# Main.net
KiCad netlist of a schematic drawn in Altium Designer
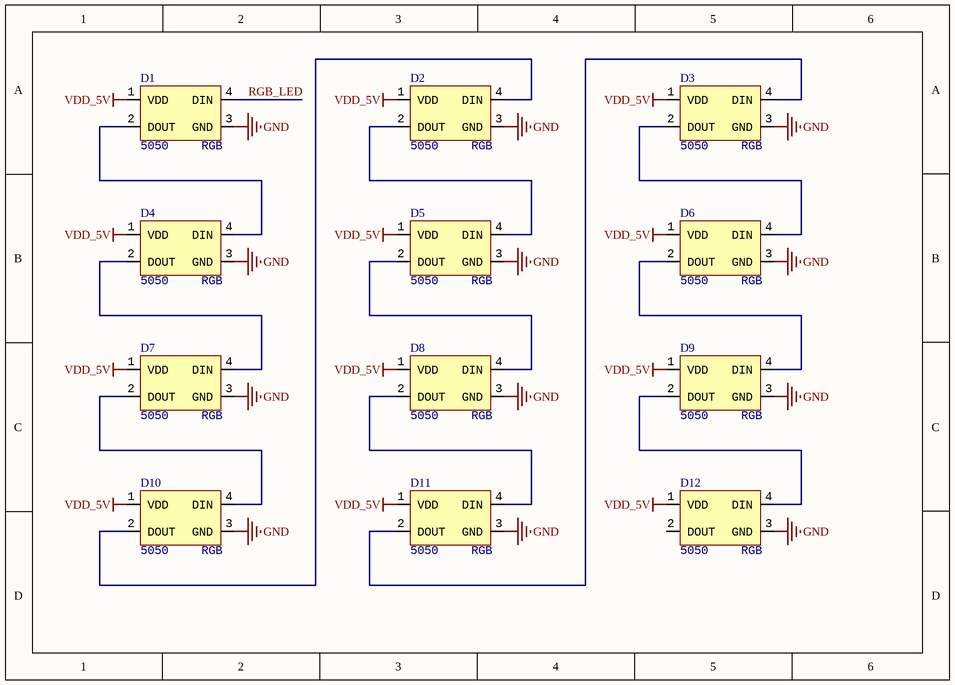
[diagram p0: Main.SchDoc]

(export (version "E")
  (design (tool "Eeschema 10.0.6"))
  (components
    (comp (ref "D1")
      (value "RGB")
      (footprint "LED_5050_WS2812B")
      (description "LED")
      (fields (field (name "TYPE") "5050"))
      (libsource (lib "KitSprout") (part "LED_5050_WS2812B"))
    )
    (comp (ref "D2")
      (value "RGB")
      (footprint "LED_5050_WS2812B")
      (description "LED")
      (fields (field (name "TYPE") "5050"))
      (libsource (lib "KitSprout") (part "LED_5050_WS2812B"))
    )
    (comp (ref "D3")
      (value "RGB")
      (footprint "LED_5050_WS2812B")
      (description "LED")
      (fields (field (name "TYPE") "5050"))
      (libsource (lib "KitSprout") (part "LED_5050_WS2812B"))
    )
    (comp (ref "D4")
      (value "RGB")
      (footprint "LED_5050_WS2812B")
      (description "LED")
      (fields (field (name "TYPE") "5050"))
      (libsource (lib "KitSprout") (part "LED_5050_WS2812B"))
    )
    (comp (ref "D5")
      (value "RGB")
      (footprint "LED_5050_WS2812B")
      (description "LED")
      (fields (field (name "TYPE") "5050"))
      (libsource (lib "KitSprout") (part "LED_5050_WS2812B"))
    )
    (comp (ref "D6")
      (value "RGB")
      (footprint "LED_5050_WS2812B")
      (description "LED")
      (fields (field (name "TYPE") "5050"))
      (libsource (lib "KitSprout") (part "LED_5050_WS2812B"))
    )
    (comp (ref "D7")
      (value "RGB")
      (footprint "LED_5050_WS2812B")
      (description "LED")
      (fields (field (name "TYPE") "5050"))
      (libsource (lib "KitSprout") (part "LED_5050_WS2812B"))
    )
    (comp (ref "D8")
      (value "RGB")
      (footprint "LED_5050_WS2812B")
      (description "LED")
      (fields (field (name "TYPE") "5050"))
      (libsource (lib "KitSprout") (part "LED_5050_WS2812B"))
    )
    (comp (ref "D9")
      (value "RGB")
      (footprint "LED_5050_WS2812B")
      (description "LED")
      (fields (field (name "TYPE") "5050"))
      (libsource (lib "KitSprout") (part "LED_5050_WS2812B"))
    )
    (comp (ref "D10")
      (value "RGB")
      (footprint "LED_5050_WS2812B")
      (description "LED")
      (fields (field (name "TYPE") "5050"))
      (libsource (lib "KitSprout") (part "LED_5050_WS2812B"))
    )
    (comp (ref "D11")
      (value "RGB")
      (footprint "LED_5050_WS2812B")
      (description "LED")
      (fields (field (name "TYPE") "5050"))
      (libsource (lib "KitSprout") (part "LED_5050_WS2812B"))
    )
    (comp (ref "D12")
      (value "RGB")
      (footprint "LED_5050_WS2812B")
      (description "LED")
      (fields (field (name "TYPE") "5050"))
      (libsource (lib "KitSprout") (part "LED_5050_WS2812B"))
    )
  )
  (nets
    (net (code "1") (name "/RGB_LED") (class "Default")
      (node (ref "D1") (pin "4") (pinfunction "DIN_4") (pintype "passive"))
    )
    (net (code "2") (name "GND") (class "Default")
      (node (ref "D1") (pin "3") (pinfunction "GND_3") (pintype "passive"))
      (node (ref "D10") (pin "3") (pinfunction "GND_3") (pintype "passive"))
      (node (ref "D11") (pin "3") (pinfunction "GND_3") (pintype "passive"))
      (node (ref "D12") (pin "3") (pinfunction "GND_3") (pintype "passive"))
      (node (ref "D2") (pin "3") (pinfunction "GND_3") (pintype "passive"))
      (node (ref "D3") (pin "3") (pinfunction "GND_3") (pintype "passive"))
      (node (ref "D4") (pin "3") (pinfunction "GND_3") (pintype "passive"))
      (node (ref "D5") (pin "3") (pinfunction "GND_3") (pintype "passive"))
      (node (ref "D6") (pin "3") (pinfunction "GND_3") (pintype "passive"))
      (node (ref "D7") (pin "3") (pinfunction "GND_3") (pintype "passive"))
      (node (ref "D8") (pin "3") (pinfunction "GND_3") (pintype "passive"))
      (node (ref "D9") (pin "3") (pinfunction "GND_3") (pintype "passive"))
    )
    (net (code "3") (name "Net-(D1-DOUT)") (class "Default")
      (node (ref "D1") (pin "2") (pinfunction "DOUT_2") (pintype "passive"))
      (node (ref "D4") (pin "4") (pinfunction "DIN_4") (pintype "passive"))
    )
    (net (code "4") (name "Net-(D2-DOUT)") (class "Default")
      (node (ref "D2") (pin "2") (pinfunction "DOUT_2") (pintype "passive"))
      (node (ref "D5") (pin "4") (pinfunction "DIN_4") (pintype "passive"))
    )
    (net (code "5") (name "Net-(D3-DOUT)") (class "Default")
      (node (ref "D3") (pin "2") (pinfunction "DOUT_2") (pintype "passive"))
      (node (ref "D6") (pin "4") (pinfunction "DIN_4") (pintype "passive"))
    )
    (net (code "6") (name "Net-(D4-DOUT)") (class "Default")
      (node (ref "D4") (pin "2") (pinfunction "DOUT_2") (pintype "passive"))
      (node (ref "D7") (pin "4") (pinfunction "DIN_4") (pintype "passive"))
    )
    (net (code "7") (name "Net-(D5-DOUT)") (class "Default")
      (node (ref "D5") (pin "2") (pinfunction "DOUT_2") (pintype "passive"))
      (node (ref "D8") (pin "4") (pinfunction "DIN_4") (pintype "passive"))
    )
    (net (code "8") (name "Net-(D6-DOUT)") (class "Default")
      (node (ref "D6") (pin "2") (pinfunction "DOUT_2") (pintype "passive"))
      (node (ref "D9") (pin "4") (pinfunction "DIN_4") (pintype "passive"))
    )
    (net (code "9") (name "Net-(D10-DIN)") (class "Default")
      (node (ref "D10") (pin "4") (pinfunction "DIN_4") (pintype "passive"))
      (node (ref "D7") (pin "2") (pinfunction "DOUT_2") (pintype "passive"))
    )
    (net (code "10") (name "Net-(D10-DOUT)") (class "Default")
      (node (ref "D10") (pin "2") (pinfunction "DOUT_2") (pintype "passive"))
      (node (ref "D2") (pin "4") (pinfunction "DIN_4") (pintype "passive"))
    )
    (net (code "11") (name "Net-(D11-DIN)") (class "Default")
      (node (ref "D11") (pin "4") (pinfunction "DIN_4") (pintype "passive"))
      (node (ref "D8") (pin "2") (pinfunction "DOUT_2") (pintype "passive"))
    )
    (net (code "12") (name "Net-(D11-DOUT)") (class "Default")
      (node (ref "D11") (pin "2") (pinfunction "DOUT_2") (pintype "passive"))
      (node (ref "D3") (pin "4") (pinfunction "DIN_4") (pintype "passive"))
    )
    (net (code "13") (name "Net-(D12-DIN)") (class "Default")
      (node (ref "D12") (pin "4") (pinfunction "DIN_4") (pintype "passive"))
      (node (ref "D9") (pin "2") (pinfunction "DOUT_2") (pintype "passive"))
    )
    (net (code "14") (name "VDD_5V") (class "Default")
      (node (ref "D1") (pin "1") (pinfunction "VDD_1") (pintype "passive"))
      (node (ref "D10") (pin "1") (pinfunction "VDD_1") (pintype "passive"))
      (node (ref "D11") (pin "1") (pinfunction "VDD_1") (pintype "passive"))
      (node (ref "D12") (pin "1") (pinfunction "VDD_1") (pintype "passive"))
      (node (ref "D2") (pin "1") (pinfunction "VDD_1") (pintype "passive"))
      (node (ref "D3") (pin "1") (pinfunction "VDD_1") (pintype "passive"))
      (node (ref "D4") (pin "1") (pinfunction "VDD_1") (pintype "passive"))
      (node (ref "D5") (pin "1") (pinfunction "VDD_1") (pintype "passive"))
      (node (ref "D6") (pin "1") (pinfunction "VDD_1") (pintype "passive"))
      (node (ref "D7") (pin "1") (pinfunction "VDD_1") (pintype "passive"))
      (node (ref "D8") (pin "1") (pinfunction "VDD_1") (pintype "passive"))
      (node (ref "D9") (pin "1") (pinfunction "VDD_1") (pintype "passive"))
    )
    (net (code "15") (name "unconnected-(D12-DOUT-Pad2)") (class "Default")
      (node (ref "D12") (pin "2") (pinfunction "DOUT_2") (pintype "passive"))
    )
  )
)
